# EHDD_LAB_5.net
KiCad netlist of a schematic drawn in EAGLE
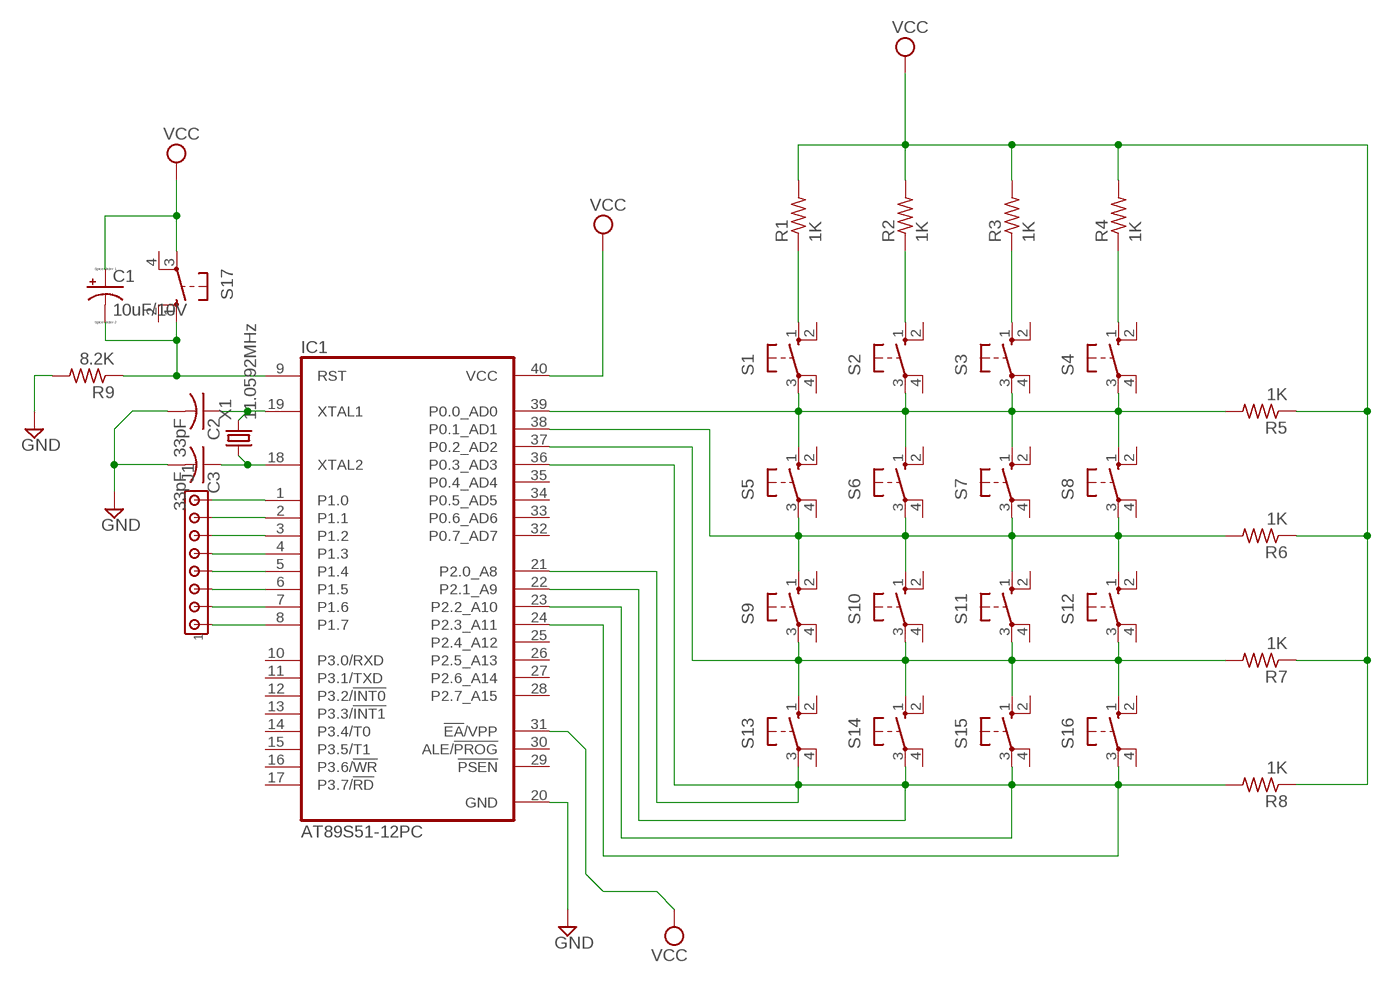
[diagram p0: schematic, sheet 1]

(export (version "E")
  (design (tool "Eeschema 10.0.6"))
  (components
    (comp (ref "C1")
      (value "10uF/10V")
      (footprint "eagle-import:153CLV-0505")
      (libsource (lib "eagle-import") (part "CPOL-US153CLV-0505"))
    )
    (comp (ref "C2")
      (value "33pF")
      (footprint "eagle-import:C0603")
      (libsource (lib "eagle-import") (part "C-USC0603"))
    )
    (comp (ref "C3")
      (value "33pF")
      (footprint "eagle-import:C0603")
      (libsource (lib "eagle-import") (part "C-USC0603"))
    )
    (comp (ref "IC1")
      (value "AT89S51-12PC")
      (footprint "eagle-import:DIL40")
      (libsource (lib "eagle-import") (part "AT89C51-PC12"))
    )
    (comp (ref "J1")
      (value "MTA08-100")
      (footprint "eagle-import:10X08MTA")
      (libsource (lib "eagle-import") (part "MTA08-100"))
    )
    (comp (ref "R1")
      (value "1K")
      (footprint "eagle-import:R0603")
      (libsource (lib "eagle-import") (part "R-US_R0603"))
    )
    (comp (ref "R2")
      (value "1K")
      (footprint "eagle-import:R0603")
      (libsource (lib "eagle-import") (part "R-US_R0603"))
    )
    (comp (ref "R3")
      (value "1K")
      (footprint "eagle-import:R0603")
      (libsource (lib "eagle-import") (part "R-US_R0603"))
    )
    (comp (ref "R4")
      (value "1K")
      (footprint "eagle-import:R0603")
      (libsource (lib "eagle-import") (part "R-US_R0603"))
    )
    (comp (ref "R5")
      (value "1K")
      (footprint "eagle-import:R0603")
      (libsource (lib "eagle-import") (part "R-US_R0603"))
    )
    (comp (ref "R6")
      (value "1K")
      (footprint "eagle-import:R0603")
      (libsource (lib "eagle-import") (part "R-US_R0603"))
    )
    (comp (ref "R7")
      (value "1K")
      (footprint "eagle-import:R0603")
      (libsource (lib "eagle-import") (part "R-US_R0603"))
    )
    (comp (ref "R8")
      (value "1K")
      (footprint "eagle-import:R0603")
      (libsource (lib "eagle-import") (part "R-US_R0603"))
    )
    (comp (ref "R9")
      (value "8.2K")
      (footprint "eagle-import:R0603")
      (libsource (lib "eagle-import") (part "R-US_R0603"))
    )
    (comp (ref "S1")
      (value "10-XX")
      (footprint "eagle-import:B3F-10XX")
      (fields (field (name "MPN") "B3F-1000"))
      (libsource (lib "eagle-import") (part "10-XX"))
    )
    (comp (ref "S2")
      (value "10-XX")
      (footprint "eagle-import:B3F-10XX")
      (fields (field (name "MPN") "B3F-1000"))
      (libsource (lib "eagle-import") (part "10-XX"))
    )
    (comp (ref "S3")
      (value "10-XX")
      (footprint "eagle-import:B3F-10XX")
      (fields (field (name "MPN") "B3F-1000"))
      (libsource (lib "eagle-import") (part "10-XX"))
    )
    (comp (ref "S4")
      (value "10-XX")
      (footprint "eagle-import:B3F-10XX")
      (fields (field (name "MPN") "B3F-1000"))
      (libsource (lib "eagle-import") (part "10-XX"))
    )
    (comp (ref "S5")
      (value "10-XX")
      (footprint "eagle-import:B3F-10XX")
      (fields (field (name "MPN") "B3F-1000"))
      (libsource (lib "eagle-import") (part "10-XX"))
    )
    (comp (ref "S6")
      (value "10-XX")
      (footprint "eagle-import:B3F-10XX")
      (fields (field (name "MPN") "B3F-1000"))
      (libsource (lib "eagle-import") (part "10-XX"))
    )
    (comp (ref "S7")
      (value "10-XX")
      (footprint "eagle-import:B3F-10XX")
      (fields (field (name "MPN") "B3F-1000"))
      (libsource (lib "eagle-import") (part "10-XX"))
    )
    (comp (ref "S8")
      (value "10-XX")
      (footprint "eagle-import:B3F-10XX")
      (fields (field (name "MPN") "B3F-1000"))
      (libsource (lib "eagle-import") (part "10-XX"))
    )
    (comp (ref "S9")
      (value "10-XX")
      (footprint "eagle-import:B3F-10XX")
      (fields (field (name "MPN") "B3F-1000"))
      (libsource (lib "eagle-import") (part "10-XX"))
    )
    (comp (ref "S10")
      (value "10-XX")
      (footprint "eagle-import:B3F-10XX")
      (fields (field (name "MPN") "B3F-1000"))
      (libsource (lib "eagle-import") (part "10-XX"))
    )
    (comp (ref "S11")
      (value "10-XX")
      (footprint "eagle-import:B3F-10XX")
      (fields (field (name "MPN") "B3F-1000"))
      (libsource (lib "eagle-import") (part "10-XX"))
    )
    (comp (ref "S12")
      (value "10-XX")
      (footprint "eagle-import:B3F-10XX")
      (fields (field (name "MPN") "B3F-1000"))
      (libsource (lib "eagle-import") (part "10-XX"))
    )
    (comp (ref "S13")
      (value "10-XX")
      (footprint "eagle-import:B3F-10XX")
      (fields (field (name "MPN") "B3F-1000"))
      (libsource (lib "eagle-import") (part "10-XX"))
    )
    (comp (ref "S14")
      (value "10-XX")
      (footprint "eagle-import:B3F-10XX")
      (fields (field (name "MPN") "B3F-1000"))
      (libsource (lib "eagle-import") (part "10-XX"))
    )
    (comp (ref "S15")
      (value "10-XX")
      (footprint "eagle-import:B3F-10XX")
      (fields (field (name "MPN") "B3F-1000"))
      (libsource (lib "eagle-import") (part "10-XX"))
    )
    (comp (ref "S16")
      (value "10-XX")
      (footprint "eagle-import:B3F-10XX")
      (fields (field (name "MPN") "B3F-1000"))
      (libsource (lib "eagle-import") (part "10-XX"))
    )
    (comp (ref "S17")
      (value "10-XX")
      (footprint "eagle-import:B3F-10XX")
      (fields (field (name "MPN") "B3F-1000"))
      (libsource (lib "eagle-import") (part "10-XX"))
    )
    (comp (ref "X1")
      (value "11.0592MHz")
      (footprint "eagle-import:HC49")
      (libsource (lib "eagle-import") (part "CRYSTALS-NOGND-HC49/4H"))
    )
  )
  (nets
    (net (code "1") (name "GND") (class "Default")
      (node (ref "C2") (pin "2") (pinfunction "2_2") (pintype "passive"))
      (node (ref "C3") (pin "2") (pinfunction "2_2") (pintype "passive"))
      (node (ref "IC1") (pin "20") (pinfunction "GND_20") (pintype "power_in"))
      (node (ref "R9") (pin "2") (pinfunction "2_2") (pintype "passive"))
    )
    (net (code "2") (name "Net-(IC1-P0.0_AD0)") (class "Default")
      (node (ref "IC1") (pin "39") (pinfunction "P0.0_AD0_39") (pintype "bidirectional"))
      (node (ref "R5") (pin "2") (pinfunction "2_2") (pintype "passive"))
      (node (ref "S1") (pin "3") (pinfunction "P_3") (pintype "passive"))
      (node (ref "S2") (pin "3") (pinfunction "P_3") (pintype "passive"))
      (node (ref "S3") (pin "3") (pinfunction "P_3") (pintype "passive"))
      (node (ref "S4") (pin "3") (pinfunction "P_3") (pintype "passive"))
      (node (ref "S5") (pin "1") (pinfunction "S_1") (pintype "passive"))
      (node (ref "S6") (pin "1") (pinfunction "S_1") (pintype "passive"))
      (node (ref "S7") (pin "1") (pinfunction "S_1") (pintype "passive"))
      (node (ref "S8") (pin "1") (pinfunction "S_1") (pintype "passive"))
    )
    (net (code "3") (name "Net-(IC1-P0.1_AD1)") (class "Default")
      (node (ref "IC1") (pin "38") (pinfunction "P0.1_AD1_38") (pintype "bidirectional"))
      (node (ref "R6") (pin "2") (pinfunction "2_2") (pintype "passive"))
      (node (ref "S10") (pin "1") (pinfunction "S_1") (pintype "passive"))
      (node (ref "S11") (pin "1") (pinfunction "S_1") (pintype "passive"))
      (node (ref "S12") (pin "1") (pinfunction "S_1") (pintype "passive"))
      (node (ref "S5") (pin "3") (pinfunction "P_3") (pintype "passive"))
      (node (ref "S6") (pin "3") (pinfunction "P_3") (pintype "passive"))
      (node (ref "S7") (pin "3") (pinfunction "P_3") (pintype "passive"))
      (node (ref "S8") (pin "3") (pinfunction "P_3") (pintype "passive"))
      (node (ref "S9") (pin "1") (pinfunction "S_1") (pintype "passive"))
    )
    (net (code "4") (name "Net-(IC1-P0.2_AD2)") (class "Default")
      (node (ref "IC1") (pin "37") (pinfunction "P0.2_AD2_37") (pintype "bidirectional"))
      (node (ref "R7") (pin "2") (pinfunction "2_2") (pintype "passive"))
      (node (ref "S10") (pin "3") (pinfunction "P_3") (pintype "passive"))
      (node (ref "S11") (pin "3") (pinfunction "P_3") (pintype "passive"))
      (node (ref "S12") (pin "3") (pinfunction "P_3") (pintype "passive"))
      (node (ref "S13") (pin "1") (pinfunction "S_1") (pintype "passive"))
      (node (ref "S14") (pin "1") (pinfunction "S_1") (pintype "passive"))
      (node (ref "S15") (pin "1") (pinfunction "S_1") (pintype "passive"))
      (node (ref "S16") (pin "1") (pinfunction "S_1") (pintype "passive"))
      (node (ref "S9") (pin "3") (pinfunction "P_3") (pintype "passive"))
    )
    (net (code "5") (name "Net-(IC1-P0.3_AD3)") (class "Default")
      (node (ref "IC1") (pin "21") (pinfunction "P2.0_A8_21") (pintype "bidirectional"))
      (node (ref "IC1") (pin "22") (pinfunction "P2.1_A9_22") (pintype "bidirectional"))
      (node (ref "IC1") (pin "23") (pinfunction "P2.2_A10_23") (pintype "bidirectional"))
      (node (ref "IC1") (pin "24") (pinfunction "P2.3_A11_24") (pintype "bidirectional"))
      (node (ref "IC1") (pin "36") (pinfunction "P0.3_AD3_36") (pintype "bidirectional"))
      (node (ref "R8") (pin "2") (pinfunction "2_2") (pintype "passive"))
      (node (ref "S13") (pin "3") (pinfunction "P_3") (pintype "passive"))
      (node (ref "S14") (pin "3") (pinfunction "P_3") (pintype "passive"))
      (node (ref "S15") (pin "3") (pinfunction "P_3") (pintype "passive"))
      (node (ref "S16") (pin "3") (pinfunction "P_3") (pintype "passive"))
    )
    (net (code "6") (name "Net-(IC1-P1.0)") (class "Default")
      (node (ref "IC1") (pin "1") (pinfunction "P1.0_1") (pintype "bidirectional"))
      (node (ref "J1") (pin "8") (pinfunction "8_8") (pintype "passive"))
    )
    (net (code "7") (name "Net-(IC1-P1.1)") (class "Default")
      (node (ref "IC1") (pin "2") (pinfunction "P1.1_2") (pintype "bidirectional"))
      (node (ref "J1") (pin "7") (pinfunction "7_7") (pintype "passive"))
    )
    (net (code "8") (name "Net-(IC1-P1.2)") (class "Default")
      (node (ref "IC1") (pin "3") (pinfunction "P1.2_3") (pintype "bidirectional"))
      (node (ref "J1") (pin "6") (pinfunction "6_6") (pintype "passive"))
    )
    (net (code "9") (name "Net-(IC1-P1.3)") (class "Default")
      (node (ref "IC1") (pin "4") (pinfunction "P1.3_4") (pintype "bidirectional"))
      (node (ref "J1") (pin "5") (pinfunction "5_5") (pintype "passive"))
    )
    (net (code "10") (name "Net-(IC1-P1.4)") (class "Default")
      (node (ref "IC1") (pin "5") (pinfunction "P1.4_5") (pintype "bidirectional"))
      (node (ref "J1") (pin "4") (pinfunction "4_4") (pintype "passive"))
    )
    (net (code "11") (name "Net-(IC1-P1.5)") (class "Default")
      (node (ref "IC1") (pin "6") (pinfunction "P1.5_6") (pintype "bidirectional"))
      (node (ref "J1") (pin "3") (pinfunction "3_3") (pintype "passive"))
    )
    (net (code "12") (name "Net-(IC1-P1.6)") (class "Default")
      (node (ref "IC1") (pin "7") (pinfunction "P1.6_7") (pintype "bidirectional"))
      (node (ref "J1") (pin "2") (pinfunction "2_2") (pintype "passive"))
    )
    (net (code "13") (name "Net-(IC1-P1.7)") (class "Default")
      (node (ref "IC1") (pin "8") (pinfunction "P1.7_8") (pintype "bidirectional"))
      (node (ref "J1") (pin "1") (pinfunction "1_1") (pintype "passive"))
    )
    (net (code "14") (name "Net-(IC1-RST)") (class "Default")
      (node (ref "C1") (pin "-") (pinfunction "-_-") (pintype "passive"))
      (node (ref "IC1") (pin "9") (pinfunction "RST_9") (pintype "input"))
      (node (ref "R9") (pin "1") (pinfunction "1_1") (pintype "passive"))
      (node (ref "S17") (pin "1") (pinfunction "S_1") (pintype "passive"))
    )
    (net (code "15") (name "Net-(IC1-XTAL1)") (class "Default")
      (node (ref "C2") (pin "1") (pinfunction "1_1") (pintype "passive"))
      (node (ref "IC1") (pin "19") (pinfunction "XTAL1_19") (pintype "input"))
      (node (ref "X1") (pin "2") (pinfunction "2_2") (pintype "passive"))
    )
    (net (code "16") (name "Net-(IC1-XTAL2)") (class "Default")
      (node (ref "C3") (pin "1") (pinfunction "1_1") (pintype "passive"))
      (node (ref "IC1") (pin "18") (pinfunction "XTAL2_18") (pintype "input"))
      (node (ref "X1") (pin "1") (pinfunction "1_1") (pintype "passive"))
    )
    (net (code "17") (name "Net-(S1-S)") (class "Default")
      (node (ref "R1") (pin "1") (pinfunction "1_1") (pintype "passive"))
      (node (ref "S1") (pin "1") (pinfunction "S_1") (pintype "passive"))
    )
    (net (code "18") (name "Net-(S2-S)") (class "Default")
      (node (ref "R2") (pin "1") (pinfunction "1_1") (pintype "passive"))
      (node (ref "S2") (pin "1") (pinfunction "S_1") (pintype "passive"))
    )
    (net (code "19") (name "Net-(S3-S)") (class "Default")
      (node (ref "R3") (pin "1") (pinfunction "1_1") (pintype "passive"))
      (node (ref "S3") (pin "1") (pinfunction "S_1") (pintype "passive"))
    )
    (net (code "20") (name "Net-(S4-S)") (class "Default")
      (node (ref "R4") (pin "1") (pinfunction "1_1") (pintype "passive"))
      (node (ref "S4") (pin "1") (pinfunction "S_1") (pintype "passive"))
    )
    (net (code "21") (name "VCC") (class "Default")
      (node (ref "C1") (pin "+") (pinfunction "+_+") (pintype "passive"))
      (node (ref "IC1") (pin "31") (pinfunction "~{EA}/VPP_31") (pintype "input"))
      (node (ref "IC1") (pin "40") (pinfunction "VCC_40") (pintype "power_in"))
      (node (ref "R1") (pin "2") (pinfunction "2_2") (pintype "passive"))
      (node (ref "R2") (pin "2") (pinfunction "2_2") (pintype "passive"))
      (node (ref "R3") (pin "2") (pinfunction "2_2") (pintype "passive"))
      (node (ref "R4") (pin "2") (pinfunction "2_2") (pintype "passive"))
      (node (ref "R5") (pin "1") (pinfunction "1_1") (pintype "passive"))
      (node (ref "R6") (pin "1") (pinfunction "1_1") (pintype "passive"))
      (node (ref "R7") (pin "1") (pinfunction "1_1") (pintype "passive"))
      (node (ref "R8") (pin "1") (pinfunction "1_1") (pintype "passive"))
      (node (ref "S17") (pin "3") (pinfunction "P_3") (pintype "passive"))
    )
    (net (code "22") (name "unconnected-(IC1-ALE{slash}~{PROG}-Pad30)") (class "Default")
      (node (ref "IC1") (pin "30") (pinfunction "ALE/~{PROG}_30") (pintype "output"))
    )
    (net (code "23") (name "unconnected-(IC1-P0.4_AD4-Pad35)") (class "Default")
      (node (ref "IC1") (pin "35") (pinfunction "P0.4_AD4_35") (pintype "bidirectional"))
    )
    (net (code "24") (name "unconnected-(IC1-P0.5_AD5-Pad34)") (class "Default")
      (node (ref "IC1") (pin "34") (pinfunction "P0.5_AD5_34") (pintype "bidirectional"))
    )
    (net (code "25") (name "unconnected-(IC1-P0.6_AD6-Pad33)") (class "Default")
      (node (ref "IC1") (pin "33") (pinfunction "P0.6_AD6_33") (pintype "bidirectional"))
    )
    (net (code "26") (name "unconnected-(IC1-P0.7_AD7-Pad32)") (class "Default")
      (node (ref "IC1") (pin "32") (pinfunction "P0.7_AD7_32") (pintype "bidirectional"))
    )
    (net (code "27") (name "unconnected-(IC1-P2.4_A12-Pad25)") (class "Default")
      (node (ref "IC1") (pin "25") (pinfunction "P2.4_A12_25") (pintype "bidirectional"))
    )
    (net (code "28") (name "unconnected-(IC1-P2.5_A13-Pad26)") (class "Default")
      (node (ref "IC1") (pin "26") (pinfunction "P2.5_A13_26") (pintype "bidirectional"))
    )
    (net (code "29") (name "unconnected-(IC1-P2.6_A14-Pad27)") (class "Default")
      (node (ref "IC1") (pin "27") (pinfunction "P2.6_A14_27") (pintype "bidirectional"))
    )
    (net (code "30") (name "unconnected-(IC1-P2.7_A15-Pad28)") (class "Default")
      (node (ref "IC1") (pin "28") (pinfunction "P2.7_A15_28") (pintype "bidirectional"))
    )
    (net (code "31") (name "unconnected-(IC1-P3.0{slash}RXD-Pad10)") (class "Default")
      (node (ref "IC1") (pin "10") (pinfunction "P3.0/RXD_10") (pintype "bidirectional"))
    )
    (net (code "32") (name "unconnected-(IC1-P3.1{slash}TXD-Pad11)") (class "Default")
      (node (ref "IC1") (pin "11") (pinfunction "P3.1/TXD_11") (pintype "bidirectional"))
    )
    (net (code "33") (name "unconnected-(IC1-P3.2{slash}~{INT0}-Pad12)") (class "Default")
      (node (ref "IC1") (pin "12") (pinfunction "P3.2/~{INT0}_12") (pintype "bidirectional"))
    )
    (net (code "34") (name "unconnected-(IC1-P3.3{slash}~{INT1}-Pad13)") (class "Default")
      (node (ref "IC1") (pin "13") (pinfunction "P3.3/~{INT1}_13") (pintype "bidirectional"))
    )
    (net (code "35") (name "unconnected-(IC1-P3.4{slash}T0-Pad14)") (class "Default")
      (node (ref "IC1") (pin "14") (pinfunction "P3.4/T0_14") (pintype "bidirectional"))
    )
    (net (code "36") (name "unconnected-(IC1-P3.5{slash}T1-Pad15)") (class "Default")
      (node (ref "IC1") (pin "15") (pinfunction "P3.5/T1_15") (pintype "bidirectional"))
    )
    (net (code "37") (name "unconnected-(IC1-P3.6{slash}~{WR}-Pad16)") (class "Default")
      (node (ref "IC1") (pin "16") (pinfunction "P3.6/~{WR}_16") (pintype "bidirectional"))
    )
    (net (code "38") (name "unconnected-(IC1-P3.7{slash}~{RD}-Pad17)") (class "Default")
      (node (ref "IC1") (pin "17") (pinfunction "P3.7/~{RD}_17") (pintype "bidirectional"))
    )
    (net (code "39") (name "unconnected-(IC1-~{PSEN}-Pad29)") (class "Default")
      (node (ref "IC1") (pin "29") (pinfunction "~{PSEN}_29") (pintype "output"))
    )
    (net (code "40") (name "unconnected-(S1-P1-Pad4)") (class "Default")
      (node (ref "S1") (pin "4") (pinfunction "P1_4") (pintype "passive"))
    )
    (net (code "41") (name "unconnected-(S1-S1-Pad2)") (class "Default")
      (node (ref "S1") (pin "2") (pinfunction "S1_2") (pintype "passive"))
    )
    (net (code "42") (name "unconnected-(S2-P1-Pad4)") (class "Default")
      (node (ref "S2") (pin "4") (pinfunction "P1_4") (pintype "passive"))
    )
    (net (code "43") (name "unconnected-(S2-S1-Pad2)") (class "Default")
      (node (ref "S2") (pin "2") (pinfunction "S1_2") (pintype "passive"))
    )
    (net (code "44") (name "unconnected-(S3-P1-Pad4)") (class "Default")
      (node (ref "S3") (pin "4") (pinfunction "P1_4") (pintype "passive"))
    )
    (net (code "45") (name "unconnected-(S3-S1-Pad2)") (class "Default")
      (node (ref "S3") (pin "2") (pinfunction "S1_2") (pintype "passive"))
    )
    (net (code "46") (name "unconnected-(S4-P1-Pad4)") (class "Default")
      (node (ref "S4") (pin "4") (pinfunction "P1_4") (pintype "passive"))
    )
    (net (code "47") (name "unconnected-(S4-S1-Pad2)") (class "Default")
      (node (ref "S4") (pin "2") (pinfunction "S1_2") (pintype "passive"))
    )
    (net (code "48") (name "unconnected-(S5-P1-Pad4)") (class "Default")
      (node (ref "S5") (pin "4") (pinfunction "P1_4") (pintype "passive"))
    )
    (net (code "49") (name "unconnected-(S5-S1-Pad2)") (class "Default")
      (node (ref "S5") (pin "2") (pinfunction "S1_2") (pintype "passive"))
    )
    (net (code "50") (name "unconnected-(S6-P1-Pad4)") (class "Default")
      (node (ref "S6") (pin "4") (pinfunction "P1_4") (pintype "passive"))
    )
    (net (code "51") (name "unconnected-(S6-S1-Pad2)") (class "Default")
      (node (ref "S6") (pin "2") (pinfunction "S1_2") (pintype "passive"))
    )
    (net (code "52") (name "unconnected-(S7-P1-Pad4)") (class "Default")
      (node (ref "S7") (pin "4") (pinfunction "P1_4") (pintype "passive"))
    )
    (net (code "53") (name "unconnected-(S7-S1-Pad2)") (class "Default")
      (node (ref "S7") (pin "2") (pinfunction "S1_2") (pintype "passive"))
    )
    (net (code "54") (name "unconnected-(S8-P1-Pad4)") (class "Default")
      (node (ref "S8") (pin "4") (pinfunction "P1_4") (pintype "passive"))
    )
    (net (code "55") (name "unconnected-(S8-S1-Pad2)") (class "Default")
      (node (ref "S8") (pin "2") (pinfunction "S1_2") (pintype "passive"))
    )
    (net (code "56") (name "unconnected-(S9-P1-Pad4)") (class "Default")
      (node (ref "S9") (pin "4") (pinfunction "P1_4") (pintype "passive"))
    )
    (net (code "57") (name "unconnected-(S9-S1-Pad2)") (class "Default")
      (node (ref "S9") (pin "2") (pinfunction "S1_2") (pintype "passive"))
    )
    (net (code "58") (name "unconnected-(S10-P1-Pad4)") (class "Default")
      (node (ref "S10") (pin "4") (pinfunction "P1_4") (pintype "passive"))
    )
    (net (code "59") (name "unconnected-(S10-S1-Pad2)") (class "Default")
      (node (ref "S10") (pin "2") (pinfunction "S1_2") (pintype "passive"))
    )
    (net (code "60") (name "unconnected-(S11-P1-Pad4)") (class "Default")
      (node (ref "S11") (pin "4") (pinfunction "P1_4") (pintype "passive"))
    )
    (net (code "61") (name "unconnected-(S11-S1-Pad2)") (class "Default")
      (node (ref "S11") (pin "2") (pinfunction "S1_2") (pintype "passive"))
    )
    (net (code "62") (name "unconnected-(S12-P1-Pad4)") (class "Default")
      (node (ref "S12") (pin "4") (pinfunction "P1_4") (pintype "passive"))
    )
    (net (code "63") (name "unconnected-(S12-S1-Pad2)") (class "Default")
      (node (ref "S12") (pin "2") (pinfunction "S1_2") (pintype "passive"))
    )
    (net (code "64") (name "unconnected-(S13-P1-Pad4)") (class "Default")
      (node (ref "S13") (pin "4") (pinfunction "P1_4") (pintype "passive"))
    )
    (net (code "65") (name "unconnected-(S13-S1-Pad2)") (class "Default")
      (node (ref "S13") (pin "2") (pinfunction "S1_2") (pintype "passive"))
    )
    (net (code "66") (name "unconnected-(S14-P1-Pad4)") (class "Default")
      (node (ref "S14") (pin "4") (pinfunction "P1_4") (pintype "passive"))
    )
    (net (code "67") (name "unconnected-(S14-S1-Pad2)") (class "Default")
      (node (ref "S14") (pin "2") (pinfunction "S1_2") (pintype "passive"))
    )
    (net (code "68") (name "unconnected-(S15-P1-Pad4)") (class "Default")
      (node (ref "S15") (pin "4") (pinfunction "P1_4") (pintype "passive"))
    )
    (net (code "69") (name "unconnected-(S15-S1-Pad2)") (class "Default")
      (node (ref "S15") (pin "2") (pinfunction "S1_2") (pintype "passive"))
    )
    (net (code "70") (name "unconnected-(S16-P1-Pad4)") (class "Default")
      (node (ref "S16") (pin "4") (pinfunction "P1_4") (pintype "passive"))
    )
    (net (code "71") (name "unconnected-(S16-S1-Pad2)") (class "Default")
      (node (ref "S16") (pin "2") (pinfunction "S1_2") (pintype "passive"))
    )
    (net (code "72") (name "unconnected-(S17-P1-Pad4)") (class "Default")
      (node (ref "S17") (pin "4") (pinfunction "P1_4") (pintype "passive"))
    )
    (net (code "73") (name "unconnected-(S17-S1-Pad2)") (class "Default")
      (node (ref "S17") (pin "2") (pinfunction "S1_2") (pintype "passive"))
    )
  )
)
